# LocationMapper.net
KiCad netlist of a schematic drawn in EAGLE
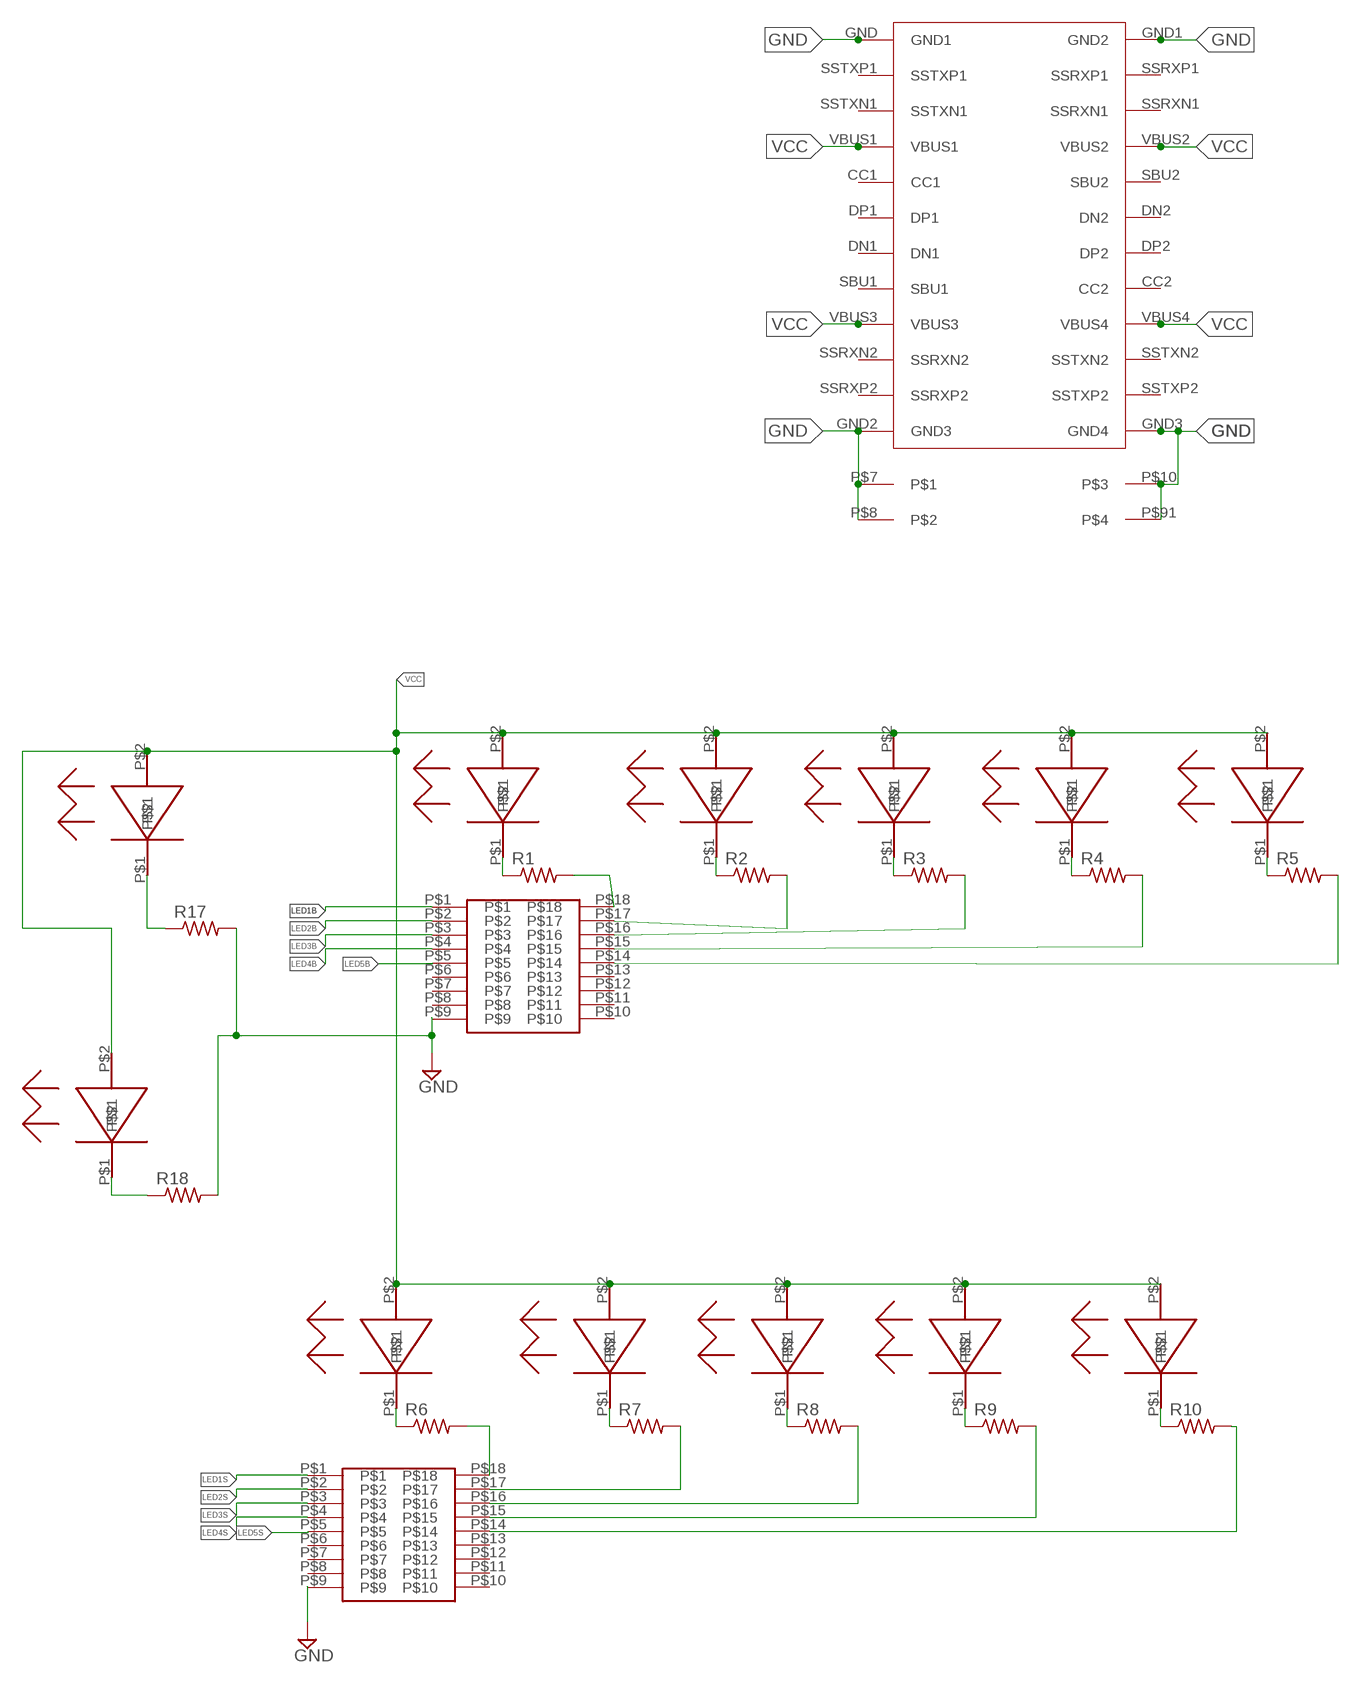
[diagram p0: schematic, sheet 1, part 1 of 2]
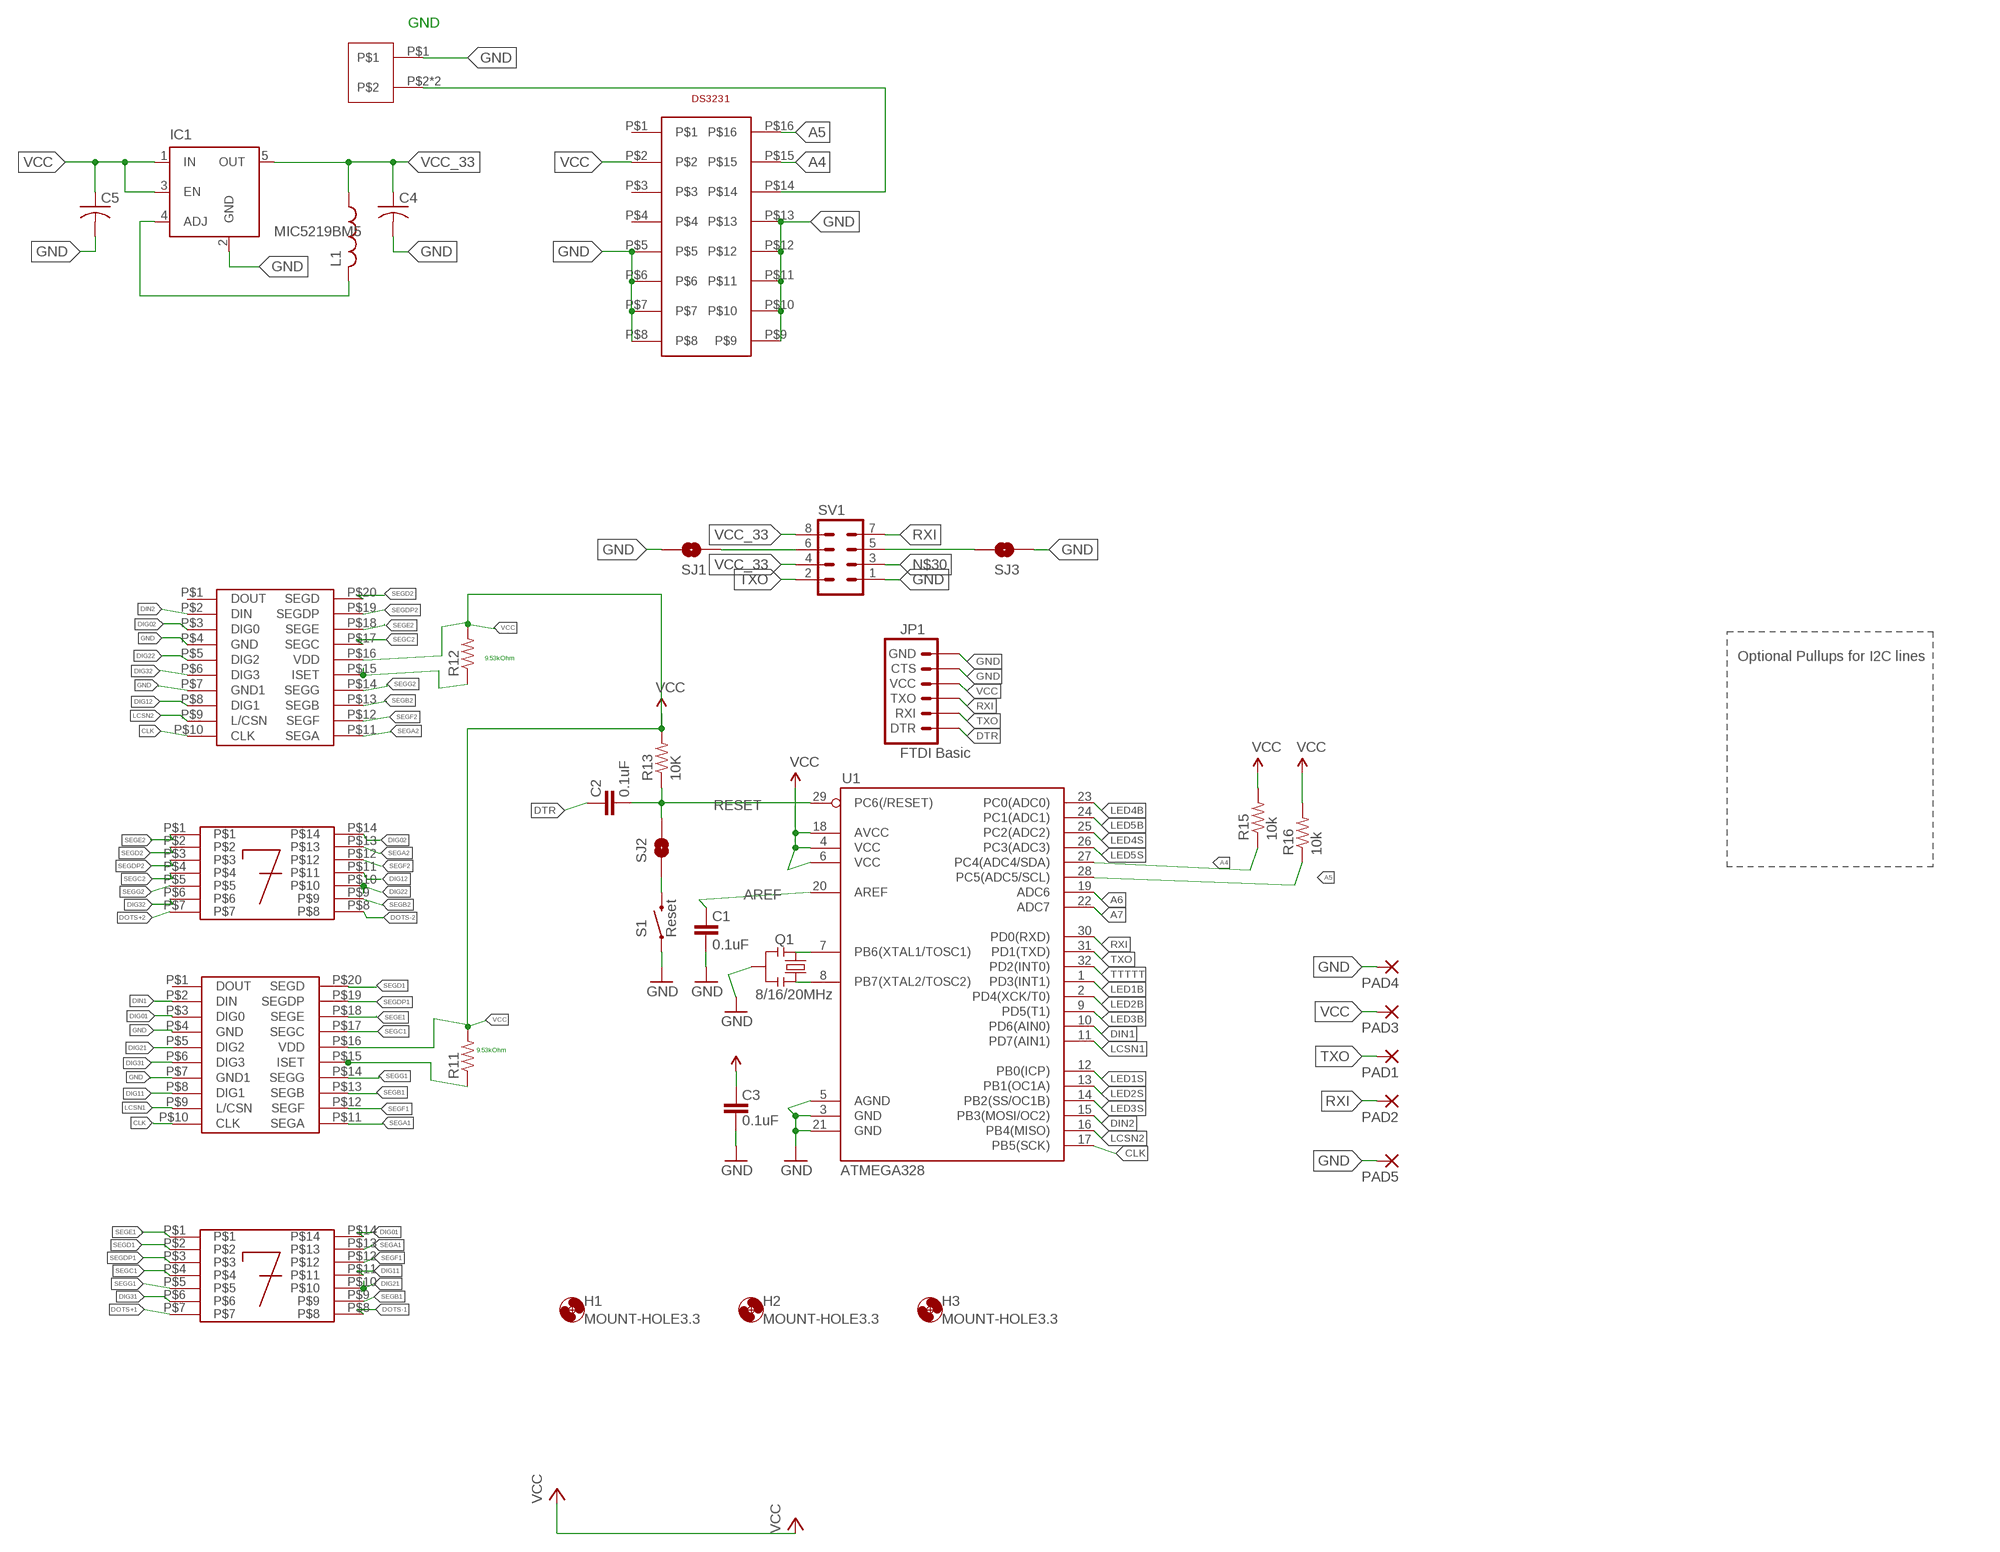
[diagram p1: schematic, sheet 1, part 2 of 2]

(export (version "E")
  (design (tool "Eeschema 10.0.6"))
  (components
    (comp (ref "C1")
      (value "0.1uF")
      (footprint "eagle-import:0603-CAP")
      (libsource (lib "eagle-import") (part "CAP0603-CAP"))
    )
    (comp (ref "C2")
      (value "0.1uF")
      (footprint "eagle-import:0603-CAP")
      (libsource (lib "eagle-import") (part "CAP0603-CAP"))
    )
    (comp (ref "C3")
      (value "0.1uF")
      (footprint "eagle-import:0603-CAP")
      (libsource (lib "eagle-import") (part "CAP0603-CAP"))
    )
    (comp (ref "C4")
      (value "C-USC0805K")
      (footprint "eagle-import:C0805K")
      (libsource (lib "eagle-import") (part "C-USC0805K"))
    )
    (comp (ref "C5")
      (value "C-USC0805K")
      (footprint "eagle-import:C0805K")
      (libsource (lib "eagle-import") (part "C-USC0805K"))
    )
    (comp (ref "H1")
      (value "MOUNT-HOLE3.3")
      (footprint "eagle-import:3,3")
      (libsource (lib "eagle-import") (part "MOUNT-HOLE3.3"))
    )
    (comp (ref "H2")
      (value "MOUNT-HOLE3.3")
      (footprint "eagle-import:3,3")
      (libsource (lib "eagle-import") (part "MOUNT-HOLE3.3"))
    )
    (comp (ref "H3")
      (value "MOUNT-HOLE3.3")
      (footprint "eagle-import:3,3")
      (libsource (lib "eagle-import") (part "MOUNT-HOLE3.3"))
    )
    (comp (ref "IC1")
      (value "MIC5219BM5")
      (footprint "eagle-import:SOT23-5")
      (fields (field (name "MF") "ALTERA CORPORATION") (field (name "MPN") "MIC5219BM5 TR"))
      (libsource (lib "eagle-import") (part "MIC5219BM5"))
    )
    (comp (ref "JP1")
      (value "FTDI Basic")
      (footprint "eagle-import:1X06")
      (libsource (lib "eagle-import") (part "ARDUINO_SERIAL_PROGRAMPTH"))
    )
    (comp (ref "L1")
      (value "L-USL2012C")
      (footprint "eagle-import:L2012C")
      (libsource (lib "eagle-import") (part "L-USL2012C"))
    )
    (comp (ref "PAD1")
      (value "2,54/1,1")
      (footprint "eagle-import:2,54_1,1")
      (libsource (lib "eagle-import") (part "2,54/1,1"))
    )
    (comp (ref "PAD2")
      (value "2,54/1,1")
      (footprint "eagle-import:2,54_1,1")
      (libsource (lib "eagle-import") (part "2,54/1,1"))
    )
    (comp (ref "PAD3")
      (value "2,54/1,1")
      (footprint "eagle-import:2,54_1,1")
      (libsource (lib "eagle-import") (part "2,54/1,1"))
    )
    (comp (ref "PAD4")
      (value "2,54/1,1")
      (footprint "eagle-import:2,54_1,1")
      (libsource (lib "eagle-import") (part "2,54/1,1"))
    )
    (comp (ref "PAD5")
      (value "2,54/1,1")
      (footprint "eagle-import:2,54_1,1")
      (libsource (lib "eagle-import") (part "2,54/1,1"))
    )
    (comp (ref "Q1")
      (value "8/16/20MHz")
      (footprint "eagle-import:RESONATOR-SMD-1_1")
      (libsource (lib "eagle-import") (part "RESONATOR1{colon}1"))
    )
    (comp (ref "R1")
      (value "R-US_R0805")
      (footprint "eagle-import:R0805")
      (libsource (lib "eagle-import") (part "R-US_R0805"))
    )
    (comp (ref "R2")
      (value "R-US_R0805")
      (footprint "eagle-import:R0805")
      (libsource (lib "eagle-import") (part "R-US_R0805"))
    )
    (comp (ref "R3")
      (value "R-US_R0805")
      (footprint "eagle-import:R0805")
      (libsource (lib "eagle-import") (part "R-US_R0805"))
    )
    (comp (ref "R4")
      (value "R-US_R0805")
      (footprint "eagle-import:R0805")
      (libsource (lib "eagle-import") (part "R-US_R0805"))
    )
    (comp (ref "R5")
      (value "R-US_R0805")
      (footprint "eagle-import:R0805")
      (libsource (lib "eagle-import") (part "R-US_R0805"))
    )
    (comp (ref "R6")
      (value "R-US_R0805")
      (footprint "eagle-import:R0805")
      (libsource (lib "eagle-import") (part "R-US_R0805"))
    )
    (comp (ref "R7")
      (value "R-US_R0805")
      (footprint "eagle-import:R0805")
      (libsource (lib "eagle-import") (part "R-US_R0805"))
    )
    (comp (ref "R8")
      (value "R-US_R0805")
      (footprint "eagle-import:R0805")
      (libsource (lib "eagle-import") (part "R-US_R0805"))
    )
    (comp (ref "R9")
      (value "R-US_R0805")
      (footprint "eagle-import:R0805")
      (libsource (lib "eagle-import") (part "R-US_R0805"))
    )
    (comp (ref "R10")
      (value "R-US_R0805")
      (footprint "eagle-import:R0805")
      (libsource (lib "eagle-import") (part "R-US_R0805"))
    )
    (comp (ref "R11")
      (value "R-US_R0805")
      (footprint "eagle-import:R0805")
      (libsource (lib "eagle-import") (part "R-US_R0805"))
    )
    (comp (ref "R12")
      (value "R-US_R0805")
      (footprint "eagle-import:R0805")
      (libsource (lib "eagle-import") (part "R-US_R0805"))
    )
    (comp (ref "R13")
      (value "10K")
      (footprint "eagle-import:0603-RES")
      (libsource (lib "eagle-import") (part "RESISTOR0603-RES"))
    )
    (comp (ref "R15")
      (value "10k")
      (footprint "eagle-import:0603-RES")
      (libsource (lib "eagle-import") (part "RESISTOR0603-RES"))
    )
    (comp (ref "R16")
      (value "10k")
      (footprint "eagle-import:0603-RES")
      (libsource (lib "eagle-import") (part "RESISTOR0603-RES"))
    )
    (comp (ref "R17")
      (value "R-US_R0805")
      (footprint "eagle-import:R0805")
      (libsource (lib "eagle-import") (part "R-US_R0805"))
    )
    (comp (ref "R18")
      (value "R-US_R0805")
      (footprint "eagle-import:R0805")
      (libsource (lib "eagle-import") (part "R-US_R0805"))
    )
    (comp (ref "S1")
      (value "Reset")
      (footprint "eagle-import:TACTILE-SWITCH-SMD-ALT01")
      (libsource (lib "eagle-import") (part "SWITCH-MOMENTARY-2SMD-ALT01"))
    )
    (comp (ref "SJ1")
      (value "SOLDERJUMPERNC")
      (footprint "eagle-import:SJ_2S")
      (libsource (lib "eagle-import") (part "SOLDERJUMPERNC"))
    )
    (comp (ref "SJ2")
      (value "SOLDERJUMPERNC")
      (footprint "eagle-import:SJ_2S")
      (libsource (lib "eagle-import") (part "SOLDERJUMPERNC"))
    )
    (comp (ref "SJ3")
      (value "SOLDERJUMPERNC")
      (footprint "eagle-import:SJ_2S")
      (libsource (lib "eagle-import") (part "SOLDERJUMPERNC"))
    )
    (comp (ref "SV1")
      (value "MA04-2")
      (footprint "eagle-import:MA04-2")
      (libsource (lib "eagle-import") (part "MA04-2"))
    )
    (comp (ref "U$1")
      (value "LED_LM")
      (footprint "eagle-import:LED_LM")
      (libsource (lib "eagle-import") (part "LED_LM"))
    )
    (comp (ref "U$2")
      (value "LED_LM")
      (footprint "eagle-import:LED_LM")
      (libsource (lib "eagle-import") (part "LED_LM"))
    )
    (comp (ref "U$3")
      (value "LED_LM")
      (footprint "eagle-import:LED_LM")
      (libsource (lib "eagle-import") (part "LED_LM"))
    )
    (comp (ref "U$4")
      (value "LED_LM")
      (footprint "eagle-import:LED_LM")
      (libsource (lib "eagle-import") (part "LED_LM"))
    )
    (comp (ref "U$5")
      (value "LED_LM")
      (footprint "eagle-import:LED_LM")
      (libsource (lib "eagle-import") (part "LED_LM"))
    )
    (comp (ref "U$6")
      (value "LED_LM")
      (footprint "eagle-import:LED_LM")
      (libsource (lib "eagle-import") (part "LED_LM"))
    )
    (comp (ref "U$7")
      (value "LED_LM")
      (footprint "eagle-import:LED_LM")
      (libsource (lib "eagle-import") (part "LED_LM"))
    )
    (comp (ref "U$8")
      (value "LED_LM")
      (footprint "eagle-import:LED_LM")
      (libsource (lib "eagle-import") (part "LED_LM"))
    )
    (comp (ref "U$9")
      (value "LED_LM")
      (footprint "eagle-import:LED_LM")
      (libsource (lib "eagle-import") (part "LED_LM"))
    )
    (comp (ref "U$10")
      (value "LED_LM")
      (footprint "eagle-import:LED_LM")
      (libsource (lib "eagle-import") (part "LED_LM"))
    )
    (comp (ref "U$11")
      (value "ULN2803A")
      (footprint "eagle-import:ULN2803A")
      (libsource (lib "eagle-import") (part "ULN2803A"))
    )
    (comp (ref "U$12")
      (value "ULN2803A")
      (footprint "eagle-import:ULN2803A")
      (libsource (lib "eagle-import") (part "ULN2803A"))
    )
    (comp (ref "U$13")
      (value "7SEG")
      (footprint "eagle-import:7SEG")
      (libsource (lib "eagle-import") (part "7SEG"))
    )
    (comp (ref "U$14")
      (value "7SEG")
      (footprint "eagle-import:7SEG")
      (libsource (lib "eagle-import") (part "7SEG"))
    )
    (comp (ref "U$15")
      (value "7SEG_DRIVER")
      (footprint "eagle-import:SO20W")
      (libsource (lib "eagle-import") (part "7SEG_DRIVER"))
    )
    (comp (ref "U$16")
      (value "7SEG_DRIVER")
      (footprint "eagle-import:SO20W")
      (libsource (lib "eagle-import") (part "7SEG_DRIVER"))
    )
    (comp (ref "U$17")
      (value "LED_LM")
      (footprint "eagle-import:LED_LM")
      (libsource (lib "eagle-import") (part "LED_LM"))
    )
    (comp (ref "U$18")
      (value "LED_LM")
      (footprint "eagle-import:LED_LM")
      (libsource (lib "eagle-import") (part "LED_LM"))
    )
    (comp (ref "U$19")
      (value "DS3231_BACK")
      (footprint "eagle-import:DS3231_BACK")
      (libsource (lib "eagle-import") (part "DS3231_BACK"))
    )
    (comp (ref "U$20")
      (value "CR2032")
      (footprint "eagle-import:CR2032")
      (libsource (lib "eagle-import") (part "CR2032"))
    )
    (comp (ref "U$21")
      (value "USB-C")
      (footprint "eagle-import:USB-C")
      (libsource (lib "eagle-import") (part "USB-C"))
    )
    (comp (ref "U1")
      (value "ATMEGA328")
      (footprint "eagle-import:TQFP32-08")
      (libsource (lib "eagle-import") (part "ATMEGA168"))
    )
  )
  (nets
    (net (code "1") (name "/AREF") (class "Default")
      (node (ref "C1") (pin "2") (pinfunction "2_2") (pintype "passive"))
      (node (ref "U1") (pin "20") (pinfunction "AREF_20") (pintype "bidirectional"))
    )
    (net (code "2") (name "/RESET") (class "Default")
      (node (ref "C2") (pin "1") (pinfunction "1_1") (pintype "passive"))
      (node (ref "R13") (pin "1") (pinfunction "1_1") (pintype "passive"))
      (node (ref "SJ2") (pin "2") (pinfunction "2_2") (pintype "passive"))
      (node (ref "U1") (pin "29") (pinfunction "PC6(/RESET)_29") (pintype "bidirectional"))
    )
    (net (code "3") (name "A4") (class "Default")
      (node (ref "R15") (pin "1") (pinfunction "1_1") (pintype "passive"))
      (node (ref "U$19") (pin "P$15") (pinfunction "P$15_P$15") (pintype "bidirectional"))
      (node (ref "U1") (pin "27") (pinfunction "PC4(ADC4/SDA)_27") (pintype "bidirectional"))
    )
    (net (code "4") (name "A5") (class "Default")
      (node (ref "R16") (pin "1") (pinfunction "1_1") (pintype "passive"))
      (node (ref "U$19") (pin "P$16") (pinfunction "P$16_P$16") (pintype "bidirectional"))
      (node (ref "U1") (pin "28") (pinfunction "PC5(ADC5/SCL)_28") (pintype "bidirectional"))
    )
    (net (code "5") (name "A6") (class "Default")
      (node (ref "U1") (pin "19") (pinfunction "ADC6_19") (pintype "bidirectional"))
    )
    (net (code "6") (name "A7") (class "Default")
      (node (ref "U1") (pin "22") (pinfunction "ADC7_22") (pintype "bidirectional"))
    )
    (net (code "7") (name "CLK") (class "Default")
      (node (ref "U$15") (pin "P$10") (pinfunction "CLK_P$10") (pintype "bidirectional"))
      (node (ref "U$16") (pin "P$10") (pinfunction "CLK_P$10") (pintype "bidirectional"))
      (node (ref "U1") (pin "17") (pinfunction "PB5(SCK)_17") (pintype "bidirectional"))
    )
    (net (code "8") (name "DIG01") (class "Default")
      (node (ref "U$14") (pin "P$14") (pinfunction "P$14_P$14") (pintype "bidirectional"))
      (node (ref "U$15") (pin "P$3") (pinfunction "DIG0_P$3") (pintype "bidirectional"))
    )
    (net (code "9") (name "DIG02") (class "Default")
      (node (ref "U$13") (pin "P$14") (pinfunction "P$14_P$14") (pintype "bidirectional"))
      (node (ref "U$16") (pin "P$3") (pinfunction "DIG0_P$3") (pintype "bidirectional"))
    )
    (net (code "10") (name "DIG11") (class "Default")
      (node (ref "U$14") (pin "P$11") (pinfunction "P$11_P$11") (pintype "bidirectional"))
      (node (ref "U$15") (pin "P$8") (pinfunction "DIG1_P$8") (pintype "bidirectional"))
    )
    (net (code "11") (name "DIG12") (class "Default")
      (node (ref "U$13") (pin "P$11") (pinfunction "P$11_P$11") (pintype "bidirectional"))
      (node (ref "U$16") (pin "P$8") (pinfunction "DIG1_P$8") (pintype "bidirectional"))
    )
    (net (code "12") (name "DIG21") (class "Default")
      (node (ref "U$14") (pin "P$10") (pinfunction "P$10_P$10") (pintype "bidirectional"))
      (node (ref "U$15") (pin "P$5") (pinfunction "DIG2_P$5") (pintype "bidirectional"))
    )
    (net (code "13") (name "DIG22") (class "Default")
      (node (ref "U$13") (pin "P$10") (pinfunction "P$10_P$10") (pintype "bidirectional"))
      (node (ref "U$16") (pin "P$5") (pinfunction "DIG2_P$5") (pintype "bidirectional"))
    )
    (net (code "14") (name "DIG31") (class "Default")
      (node (ref "U$14") (pin "P$6") (pinfunction "P$6_P$6") (pintype "bidirectional"))
      (node (ref "U$15") (pin "P$6") (pinfunction "DIG3_P$6") (pintype "bidirectional"))
    )
    (net (code "15") (name "DIG32") (class "Default")
      (node (ref "U$13") (pin "P$6") (pinfunction "P$6_P$6") (pintype "bidirectional"))
      (node (ref "U$16") (pin "P$6") (pinfunction "DIG3_P$6") (pintype "bidirectional"))
    )
    (net (code "16") (name "DIN1") (class "Default")
      (node (ref "U$15") (pin "P$2") (pinfunction "DIN_P$2") (pintype "bidirectional"))
      (node (ref "U1") (pin "10") (pinfunction "PD6(AIN0)_10") (pintype "bidirectional"))
    )
    (net (code "17") (name "DIN2") (class "Default")
      (node (ref "U$16") (pin "P$2") (pinfunction "DIN_P$2") (pintype "bidirectional"))
      (node (ref "U1") (pin "15") (pinfunction "PB3(MOSI/OC2)_15") (pintype "bidirectional"))
    )
    (net (code "18") (name "DOTS+1") (class "Default")
      (node (ref "U$14") (pin "P$7") (pinfunction "P$7_P$7") (pintype "bidirectional"))
    )
    (net (code "19") (name "DOTS+2") (class "Default")
      (node (ref "U$13") (pin "P$7") (pinfunction "P$7_P$7") (pintype "bidirectional"))
    )
    (net (code "20") (name "DOTS-1") (class "Default")
      (node (ref "U$14") (pin "P$8") (pinfunction "P$8_P$8") (pintype "bidirectional"))
    )
    (net (code "21") (name "DOTS-2") (class "Default")
      (node (ref "U$13") (pin "P$8") (pinfunction "P$8_P$8") (pintype "bidirectional"))
    )
    (net (code "22") (name "DTR") (class "Default")
      (node (ref "C2") (pin "2") (pinfunction "2_2") (pintype "passive"))
      (node (ref "JP1") (pin "1") (pinfunction "DTR_1") (pintype "passive"))
    )
    (net (code "23") (name "GND") (class "Default")
      (node (ref "C1") (pin "1") (pinfunction "1_1") (pintype "passive"))
      (node (ref "C3") (pin "1") (pinfunction "1_1") (pintype "passive"))
      (node (ref "C4") (pin "2") (pinfunction "2_2") (pintype "passive"))
      (node (ref "C5") (pin "2") (pinfunction "2_2") (pintype "passive"))
      (node (ref "IC1") (pin "2") (pinfunction "GND_2") (pintype "power_in"))
      (node (ref "JP1") (pin "5") (pinfunction "CTS_5") (pintype "passive"))
      (node (ref "JP1") (pin "6") (pinfunction "GND_6") (pintype "passive"))
      (node (ref "PAD4") (pin "1") (pinfunction "P_1") (pintype "passive"))
      (node (ref "PAD5") (pin "1") (pinfunction "P_1") (pintype "passive"))
      (node (ref "Q1") (pin "2") (pinfunction "2_2") (pintype "passive"))
      (node (ref "R17") (pin "2") (pinfunction "2_2") (pintype "passive"))
      (node (ref "R18") (pin "2") (pinfunction "2_2") (pintype "passive"))
      (node (ref "S1") (pin "1") (pinfunction "1_1") (pintype "passive"))
      (node (ref "S1") (pin "2") (pinfunction "1_2") (pintype "passive"))
      (node (ref "SJ1") (pin "2") (pinfunction "2_2") (pintype "passive"))
      (node (ref "SJ3") (pin "1") (pinfunction "1_1") (pintype "passive"))
      (node (ref "SV1") (pin "1") (pinfunction "1_1") (pintype "passive"))
      (node (ref "U$11") (pin "P$9") (pinfunction "P$9_P$9") (pintype "bidirectional"))
      (node (ref "U$12") (pin "P$9") (pinfunction "P$9_P$9") (pintype "bidirectional"))
      (node (ref "U$15") (pin "P$4") (pinfunction "GND_P$4") (pintype "bidirectional"))
      (node (ref "U$15") (pin "P$7") (pinfunction "GND1_P$7") (pintype "bidirectional"))
      (node (ref "U$16") (pin "P$4") (pinfunction "GND_P$4") (pintype "bidirectional"))
      (node (ref "U$16") (pin "P$7") (pinfunction "GND1_P$7") (pintype "bidirectional"))
      (node (ref "U$19") (pin "P$10") (pinfunction "P$10_P$10") (pintype "bidirectional"))
      (node (ref "U$19") (pin "P$11") (pinfunction "P$11_P$11") (pintype "bidirectional"))
      (node (ref "U$19") (pin "P$12") (pinfunction "P$12_P$12") (pintype "bidirectional"))
      (node (ref "U$19") (pin "P$13") (pinfunction "P$13_P$13") (pintype "bidirectional"))
      (node (ref "U$19") (pin "P$5") (pinfunction "P$5_P$5") (pintype "bidirectional"))
      (node (ref "U$19") (pin "P$6") (pinfunction "P$6_P$6") (pintype "bidirectional"))
      (node (ref "U$19") (pin "P$7") (pinfunction "P$7_P$7") (pintype "bidirectional"))
      (node (ref "U$19") (pin "P$8") (pinfunction "P$8_P$8") (pintype "bidirectional"))
      (node (ref "U$19") (pin "P$9") (pinfunction "P$9_P$9") (pintype "bidirectional"))
      (node (ref "U$20") (pin "P$1") (pinfunction "P$1_P$1") (pintype "bidirectional"))
      (node (ref "U$21") (pin "GND") (pinfunction "GND1_GND") (pintype "bidirectional"))
      (node (ref "U$21") (pin "GND1") (pinfunction "GND2_GND1") (pintype "bidirectional"))
      (node (ref "U$21") (pin "GND2") (pinfunction "GND3_GND2") (pintype "bidirectional"))
      (node (ref "U$21") (pin "GND3") (pinfunction "GND4_GND3") (pintype "bidirectional"))
      (node (ref "U$21") (pin "P$10") (pinfunction "P$3_P$10") (pintype "bidirectional"))
      (node (ref "U$21") (pin "P$7") (pinfunction "P$1_P$7") (pintype "bidirectional"))
      (node (ref "U$21") (pin "P$8") (pinfunction "P$2_P$8") (pintype "bidirectional"))
      (node (ref "U$21") (pin "P$91") (pinfunction "P$4_P$91") (pintype "bidirectional"))
      (node (ref "U1") (pin "21") (pinfunction "GND_21") (pintype "bidirectional"))
      (node (ref "U1") (pin "3") (pinfunction "GND_3") (pintype "bidirectional"))
      (node (ref "U1") (pin "5") (pinfunction "AGND_5") (pintype "bidirectional"))
    )
    (net (code "24") (name "LCSN1") (class "Default")
      (node (ref "U$15") (pin "P$9") (pinfunction "L/CSN_P$9") (pintype "bidirectional"))
      (node (ref "U1") (pin "11") (pinfunction "PD7(AIN1)_11") (pintype "bidirectional"))
    )
    (net (code "25") (name "LCSN2") (class "Default")
      (node (ref "U$16") (pin "P$9") (pinfunction "L/CSN_P$9") (pintype "bidirectional"))
      (node (ref "U1") (pin "16") (pinfunction "PB4(MISO)_16") (pintype "bidirectional"))
    )
    (net (code "26") (name "LED1B") (class "Default")
      (node (ref "U$11") (pin "P$1") (pinfunction "P$1_P$1") (pintype "bidirectional"))
      (node (ref "U1") (pin "1") (pinfunction "PD3(INT1)_1") (pintype "bidirectional"))
    )
    (net (code "27") (name "LED1S") (class "Default")
      (node (ref "U$12") (pin "P$1") (pinfunction "P$1_P$1") (pintype "bidirectional"))
      (node (ref "U1") (pin "12") (pinfunction "PB0(ICP)_12") (pintype "bidirectional"))
    )
    (net (code "28") (name "LED2B") (class "Default")
      (node (ref "U$11") (pin "P$2") (pinfunction "P$2_P$2") (pintype "bidirectional"))
      (node (ref "U1") (pin "2") (pinfunction "PD4(XCK/T0)_2") (pintype "bidirectional"))
    )
    (net (code "29") (name "LED2S") (class "Default")
      (node (ref "U$12") (pin "P$2") (pinfunction "P$2_P$2") (pintype "bidirectional"))
      (node (ref "U1") (pin "13") (pinfunction "PB1(OC1A)_13") (pintype "bidirectional"))
    )
    (net (code "30") (name "LED3B") (class "Default")
      (node (ref "U$11") (pin "P$3") (pinfunction "P$3_P$3") (pintype "bidirectional"))
      (node (ref "U1") (pin "9") (pinfunction "PD5(T1)_9") (pintype "bidirectional"))
    )
    (net (code "31") (name "LED3S") (class "Default")
      (node (ref "U$12") (pin "P$3") (pinfunction "P$3_P$3") (pintype "bidirectional"))
      (node (ref "U1") (pin "14") (pinfunction "PB2(SS/OC1B)_14") (pintype "bidirectional"))
    )
    (net (code "32") (name "LED4B") (class "Default")
      (node (ref "U$11") (pin "P$4") (pinfunction "P$4_P$4") (pintype "bidirectional"))
      (node (ref "U1") (pin "23") (pinfunction "PC0(ADC0)_23") (pintype "bidirectional"))
    )
    (net (code "33") (name "LED4S") (class "Default")
      (node (ref "U$12") (pin "P$4") (pinfunction "P$4_P$4") (pintype "bidirectional"))
      (node (ref "U1") (pin "25") (pinfunction "PC2(ADC2)_25") (pintype "bidirectional"))
    )
    (net (code "34") (name "LED5B") (class "Default")
      (node (ref "U$11") (pin "P$5") (pinfunction "P$5_P$5") (pintype "bidirectional"))
      (node (ref "U1") (pin "24") (pinfunction "PC1(ADC1)_24") (pintype "bidirectional"))
    )
    (net (code "35") (name "LED5S") (class "Default")
      (node (ref "U$12") (pin "P$5") (pinfunction "P$5_P$5") (pintype "bidirectional"))
      (node (ref "U1") (pin "26") (pinfunction "PC3(ADC3)_26") (pintype "bidirectional"))
    )
    (net (code "36") (name "N$30") (class "Default")
      (node (ref "SV1") (pin "3") (pinfunction "3_3") (pintype "passive"))
    )
    (net (code "37") (name "Net-(IC1-ADJ)") (class "Default")
      (node (ref "IC1") (pin "4") (pinfunction "ADJ_4") (pintype "passive"))
      (node (ref "L1") (pin "2") (pinfunction "2_2") (pintype "passive"))
    )
    (net (code "38") (name "Net-(R1-Pad1)") (class "Default")
      (node (ref "R1") (pin "1") (pinfunction "1_1") (pintype "passive"))
      (node (ref "U$6") (pin "P$1") (pinfunction "P$1_P$1") (pintype "bidirectional"))
    )
    (net (code "39") (name "Net-(R1-Pad2)") (class "Default")
      (node (ref "R1") (pin "2") (pinfunction "2_2") (pintype "passive"))
      (node (ref "U$11") (pin "P$18") (pinfunction "P$18_P$18") (pintype "bidirectional"))
    )
    (net (code "40") (name "Net-(R2-Pad1)") (class "Default")
      (node (ref "R2") (pin "1") (pinfunction "1_1") (pintype "passive"))
      (node (ref "U$7") (pin "P$1") (pinfunction "P$1_P$1") (pintype "bidirectional"))
    )
    (net (code "41") (name "Net-(R2-Pad2)") (class "Default")
      (node (ref "R2") (pin "2") (pinfunction "2_2") (pintype "passive"))
      (node (ref "U$11") (pin "P$17") (pinfunction "P$17_P$17") (pintype "bidirectional"))
    )
    (net (code "42") (name "Net-(R3-Pad1)") (class "Default")
      (node (ref "R3") (pin "1") (pinfunction "1_1") (pintype "passive"))
      (node (ref "U$8") (pin "P$1") (pinfunction "P$1_P$1") (pintype "bidirectional"))
    )
    (net (code "43") (name "Net-(R3-Pad2)") (class "Default")
      (node (ref "R3") (pin "2") (pinfunction "2_2") (pintype "passive"))
      (node (ref "U$11") (pin "P$16") (pinfunction "P$16_P$16") (pintype "bidirectional"))
    )
    (net (code "44") (name "Net-(R4-Pad1)") (class "Default")
      (node (ref "R4") (pin "1") (pinfunction "1_1") (pintype "passive"))
      (node (ref "U$9") (pin "P$1") (pinfunction "P$1_P$1") (pintype "bidirectional"))
    )
    (net (code "45") (name "Net-(R4-Pad2)") (class "Default")
      (node (ref "R4") (pin "2") (pinfunction "2_2") (pintype "passive"))
      (node (ref "U$11") (pin "P$15") (pinfunction "P$15_P$15") (pintype "bidirectional"))
    )
    (net (code "46") (name "Net-(R5-Pad1)") (class "Default")
      (node (ref "R5") (pin "1") (pinfunction "1_1") (pintype "passive"))
      (node (ref "U$10") (pin "P$1") (pinfunction "P$1_P$1") (pintype "bidirectional"))
    )
    (net (code "47") (name "Net-(R5-Pad2)") (class "Default")
      (node (ref "R5") (pin "2") (pinfunction "2_2") (pintype "passive"))
      (node (ref "U$11") (pin "P$14") (pinfunction "P$14_P$14") (pintype "bidirectional"))
    )
    (net (code "48") (name "Net-(R6-Pad1)") (class "Default")
      (node (ref "R6") (pin "1") (pinfunction "1_1") (pintype "passive"))
      (node (ref "U$1") (pin "P$1") (pinfunction "P$1_P$1") (pintype "bidirectional"))
    )
    (net (code "49") (name "Net-(R6-Pad2)") (class "Default")
      (node (ref "R6") (pin "2") (pinfunction "2_2") (pintype "passive"))
      (node (ref "U$12") (pin "P$18") (pinfunction "P$18_P$18") (pintype "bidirectional"))
    )
    (net (code "50") (name "Net-(R7-Pad1)") (class "Default")
      (node (ref "R7") (pin "1") (pinfunction "1_1") (pintype "passive"))
      (node (ref "U$2") (pin "P$1") (pinfunction "P$1_P$1") (pintype "bidirectional"))
    )
    (net (code "51") (name "Net-(R7-Pad2)") (class "Default")
      (node (ref "R7") (pin "2") (pinfunction "2_2") (pintype "passive"))
      (node (ref "U$12") (pin "P$17") (pinfunction "P$17_P$17") (pintype "bidirectional"))
    )
    (net (code "52") (name "Net-(R8-Pad1)") (class "Default")
      (node (ref "R8") (pin "1") (pinfunction "1_1") (pintype "passive"))
      (node (ref "U$3") (pin "P$1") (pinfunction "P$1_P$1") (pintype "bidirectional"))
    )
    (net (code "53") (name "Net-(R8-Pad2)") (class "Default")
      (node (ref "R8") (pin "2") (pinfunction "2_2") (pintype "passive"))
      (node (ref "U$12") (pin "P$16") (pinfunction "P$16_P$16") (pintype "bidirectional"))
    )
    (net (code "54") (name "Net-(R9-Pad1)") (class "Default")
      (node (ref "R9") (pin "1") (pinfunction "1_1") (pintype "passive"))
      (node (ref "U$4") (pin "P$1") (pinfunction "P$1_P$1") (pintype "bidirectional"))
    )
    (net (code "55") (name "Net-(R9-Pad2)") (class "Default")
      (node (ref "R9") (pin "2") (pinfunction "2_2") (pintype "passive"))
      (node (ref "U$12") (pin "P$15") (pinfunction "P$15_P$15") (pintype "bidirectional"))
    )
    (net (code "56") (name "Net-(R10-Pad1)") (class "Default")
      (node (ref "R10") (pin "1") (pinfunction "1_1") (pintype "passive"))
      (node (ref "U$5") (pin "P$1") (pinfunction "P$1_P$1") (pintype "bidirectional"))
    )
    (net (code "57") (name "Net-(R10-Pad2)") (class "Default")
      (node (ref "R10") (pin "2") (pinfunction "2_2") (pintype "passive"))
      (node (ref "U$12") (pin "P$14") (pinfunction "P$14_P$14") (pintype "bidirectional"))
    )
    (net (code "58") (name "Net-(R17-Pad1)") (class "Default")
      (node (ref "R17") (pin "1") (pinfunction "1_1") (pintype "passive"))
      (node (ref "U$17") (pin "P$1") (pinfunction "P$1_P$1") (pintype "bidirectional"))
    )
    (net (code "59") (name "Net-(R18-Pad1)") (class "Default")
      (node (ref "R18") (pin "1") (pinfunction "1_1") (pintype "passive"))
      (node (ref "U$18") (pin "P$1") (pinfunction "P$1_P$1") (pintype "bidirectional"))
    )
    (net (code "60") (name "Net-(S1-2-Pad3)") (class "Default")
      (node (ref "S1") (pin "3") (pinfunction "2_3") (pintype "passive"))
      (node (ref "S1") (pin "4") (pinfunction "2_4") (pintype "passive"))
      (node (ref "SJ2") (pin "1") (pinfunction "1_1") (pintype "passive"))
    )
    (net (code "61") (name "Net-(SJ1-Pad1)") (class "Default")
      (node (ref "SJ1") (pin "1") (pinfunction "1_1") (pintype "passive"))
      (node (ref "SV1") (pin "6") (pinfunction "6_6") (pintype "passive"))
    )
    (net (code "62") (name "Net-(SJ3-Pad2)") (class "Default")
      (node (ref "SJ3") (pin "2") (pinfunction "2_2") (pintype "passive"))
      (node (ref "SV1") (pin "5") (pinfunction "5_5") (pintype "passive"))
    )
    (net (code "63") (name "Net-(U$15-ISET)") (class "Default")
      (node (ref "R11") (pin "1") (pinfunction "1_1") (pintype "passive"))
      (node (ref "U$15") (pin "P$15") (pinfunction "ISET_P$15") (pintype "bidirectional"))
    )
    (net (code "64") (name "Net-(U$16-ISET)") (class "Default")
      (node (ref "R12") (pin "1") (pinfunction "1_1") (pintype "passive"))
      (node (ref "U$16") (pin "P$15") (pinfunction "ISET_P$15") (pintype "bidirectional"))
    )
    (net (code "65") (name "Net-(U$19-PadP$14)") (class "Default")
      (node (ref "U$19") (pin "P$14") (pinfunction "P$14_P$14") (pintype "bidirectional"))
      (node (ref "U$20") (pin "P$2") (pinfunction "P$2_P$2") (pintype "bidirectional"))
      (node (ref "U$20") (pin "P$3") (pinfunction "P$2_P$3") (pintype "bidirectional"))
    )
    (net (code "66") (name "Net-(U1-PB6(XTAL1{slash}TOSC1))") (class "Default")
      (node (ref "Q1") (pin "1") (pinfunction "1_1") (pintype "passive"))
      (node (ref "U1") (pin "7") (pinfunction "PB6(XTAL1/TOSC1)_7") (pintype "bidirectional"))
    )
    (net (code "67") (name "Net-(U1-PB7(XTAL2{slash}TOSC2))") (class "Default")
      (node (ref "Q1") (pin "3") (pinfunction "3_3") (pintype "passive"))
      (node (ref "U1") (pin "8") (pinfunction "PB7(XTAL2/TOSC2)_8") (pintype "bidirectional"))
    )
    (net (code "68") (name "RXI") (class "Default")
      (node (ref "JP1") (pin "3") (pinfunction "TXO_3") (pintype "passive"))
      (node (ref "PAD2") (pin "1") (pinfunction "P_1") (pintype "passive"))
      (node (ref "SV1") (pin "7") (pinfunction "7_7") (pintype "passive"))
      (node (ref "U1") (pin "30") (pinfunction "PD0(RXD)_30") (pintype "bidirectional"))
    )
    (net (code "69") (name "SEGA1") (class "Default")
      (node (ref "U$14") (pin "P$13") (pinfunction "P$13_P$13") (pintype "bidirectional"))
      (node (ref "U$15") (pin "P$11") (pinfunction "SEGA_P$11") (pintype "bidirectional"))
    )
    (net (code "70") (name "SEGA2") (class "Default")
      (node (ref "U$13") (pin "P$13") (pinfunction "P$13_P$13") (pintype "bidirectional"))
      (node (ref "U$16") (pin "P$11") (pinfunction "SEGA_P$11") (pintype "bidirectional"))
    )
    (net (code "71") (name "SEGB1") (class "Default")
      (node (ref "U$14") (pin "P$9") (pinfunction "P$9_P$9") (pintype "bidirectional"))
      (node (ref "U$15") (pin "P$13") (pinfunction "SEGB_P$13") (pintype "bidirectional"))
    )
    (net (code "72") (name "SEGB2") (class "Default")
      (node (ref "U$13") (pin "P$9") (pinfunction "P$9_P$9") (pintype "bidirectional"))
      (node (ref "U$16") (pin "P$13") (pinfunction "SEGB_P$13") (pintype "bidirectional"))
    )
    (net (code "73") (name "SEGC1") (class "Default")
      (node (ref "U$14") (pin "P$4") (pinfunction "P$4_P$4") (pintype "bidirectional"))
      (node (ref "U$15") (pin "P$17") (pinfunction "SEGC_P$17") (pintype "bidirectional"))
    )
    (net (code "74") (name "SEGC2") (class "Default")
      (node (ref "U$13") (pin "P$4") (pinfunction "P$4_P$4") (pintype "bidirectional"))
      (node (ref "U$16") (pin "P$17") (pinfunction "SEGC_P$17") (pintype "bidirectional"))
    )
    (net (code "75") (name "SEGD1") (class "Default")
      (node (ref "U$14") (pin "P$2") (pinfunction "P$2_P$2") (pintype "bidirectional"))
      (node (ref "U$15") (pin "P$20") (pinfunction "SEGD_P$20") (pintype "bidirectional"))
    )
    (net (code "76") (name "SEGD2") (class "Default")
      (node (ref "U$13") (pin "P$2") (pinfunction "P$2_P$2") (pintype "bidirectional"))
      (node (ref "U$16") (pin "P$20") (pinfunction "SEGD_P$20") (pintype "bidirectional"))
    )
    (net (code "77") (name "SEGDP1") (class "Default")
      (node (ref "U$14") (pin "P$3") (pinfunction "P$3_P$3") (pintype "bidirectional"))
      (node (ref "U$15") (pin "P$19") (pinfunction "SEGDP_P$19") (pintype "bidirectional"))
    )
    (net (code "78") (name "SEGDP2") (class "Default")
      (node (ref "U$13") (pin "P$3") (pinfunction "P$3_P$3") (pintype "bidirectional"))
      (node (ref "U$16") (pin "P$19") (pinfunction "SEGDP_P$19") (pintype "bidirectional"))
    )
    (net (code "79") (name "SEGE1") (class "Default")
      (node (ref "U$14") (pin "P$1") (pinfunction "P$1_P$1") (pintype "bidirectional"))
      (node (ref "U$15") (pin "P$18") (pinfunction "SEGE_P$18") (pintype "bidirectional"))
    )
    (net (code "80") (name "SEGE2") (class "Default")
      (node (ref "U$13") (pin "P$1") (pinfunction "P$1_P$1") (pintype "bidirectional"))
      (node (ref "U$16") (pin "P$18") (pinfunction "SEGE_P$18") (pintype "bidirectional"))
    )
    (net (code "81") (name "SEGF1") (class "Default")
      (node (ref "U$14") (pin "P$12") (pinfunction "P$12_P$12") (pintype "bidirectional"))
      (node (ref "U$15") (pin "P$12") (pinfunction "SEGF_P$12") (pintype "bidirectional"))
    )
    (net (code "82") (name "SEGF2") (class "Default")
      (node (ref "U$13") (pin "P$12") (pinfunction "P$12_P$12") (pintype "bidirectional"))
      (node (ref "U$16") (pin "P$12") (pinfunction "SEGF_P$12") (pintype "bidirectional"))
    )
    (net (code "83") (name "SEGG1") (class "Default")
      (node (ref "U$14") (pin "P$5") (pinfunction "P$5_P$5") (pintype "bidirectional"))
      (node (ref "U$15") (pin "P$14") (pinfunction "SEGG_P$14") (pintype "bidirectional"))
    )
    (net (code "84") (name "SEGG2") (class "Default")
      (node (ref "U$13") (pin "P$5") (pinfunction "P$5_P$5") (pintype "bidirectional"))
      (node (ref "U$16") (pin "P$14") (pinfunction "SEGG_P$14") (pintype "bidirectional"))
    )
    (net (code "85") (name "TTTTT") (class "Default")
      (node (ref "U1") (pin "32") (pinfunction "PD2(INT0)_32") (pintype "bidirectional"))
    )
    (net (code "86") (name "TXO") (class "Default")
      (node (ref "JP1") (pin "2") (pinfunction "RXI_2") (pintype "passive"))
      (node (ref "PAD1") (pin "1") (pinfunction "P_1") (pintype "passive"))
      (node (ref "SV1") (pin "2") (pinfunction "2_2") (pintype "passive"))
      (node (ref "U1") (pin "31") (pinfunction "PD1(TXD)_31") (pintype "bidirectional"))
    )
    (net (code "87") (name "VCC") (class "Default")
      (node (ref "C3") (pin "2") (pinfunction "2_2") (pintype "passive"))
      (node (ref "C5") (pin "1") (pinfunction "1_1") (pintype "passive"))
      (node (ref "IC1") (pin "1") (pinfunction "IN_1") (pintype "input"))
      (node (ref "IC1") (pin "3") (pinfunction "EN_3") (pintype "input"))
      (node (ref "JP1") (pin "4") (pinfunction "VCC_4") (pintype "passive"))
      (node (ref "PAD3") (pin "1") (pinfunction "P_1") (pintype "passive"))
      (node (ref "R11") (pin "2") (pinfunction "2_2") (pintype "passive"))
      (node (ref "R12") (pin "2") (pinfunction "2_2") (pintype "passive"))
      (node (ref "R13") (pin "2") (pinfunction "2_2") (pintype "passive"))
      (node (ref "R15") (pin "2") (pinfunction "2_2") (pintype "passive"))
      (node (ref "R16") (pin "2") (pinfunction "2_2") (pintype "passive"))
      (node (ref "U$1") (pin "P$2") (pinfunction "P$2_P$2") (pintype "bidirectional"))
      (node (ref "U$10") (pin "P$2") (pinfunction "P$2_P$2") (pintype "bidirectional"))
      (node (ref "U$15") (pin "P$16") (pinfunction "VDD_P$16") (pintype "bidirectional"))
      (node (ref "U$16") (pin "P$16") (pinfunction "VDD_P$16") (pintype "bidirectional"))
      (node (ref "U$17") (pin "P$2") (pinfunction "P$2_P$2") (pintype "bidirectional"))
      (node (ref "U$18") (pin "P$2") (pinfunction "P$2_P$2") (pintype "bidirectional"))
      (node (ref "U$19") (pin "P$2") (pinfunction "P$2_P$2") (pintype "bidirectional"))
      (node (ref "U$2") (pin "P$2") (pinfunction "P$2_P$2") (pintype "bidirectional"))
      (node (ref "U$21") (pin "VBUS1") (pinfunction "VBUS1_VBUS1") (pintype "bidirectional"))
      (node (ref "U$21") (pin "VBUS2") (pinfunction "VBUS2_VBUS2") (pintype "bidirectional"))
      (node (ref "U$21") (pin "VBUS3") (pinfunction "VBUS3_VBUS3") (pintype "bidirectional"))
      (node (ref "U$21") (pin "VBUS4") (pinfunction "VBUS4_VBUS4") (pintype "bidirectional"))
      (node (ref "U$3") (pin "P$2") (pinfunction "P$2_P$2") (pintype "bidirectional"))
      (node (ref "U$4") (pin "P$2") (pinfunction "P$2_P$2") (pintype "bidirectional"))
      (node (ref "U$5") (pin "P$2") (pinfunction "P$2_P$2") (pintype "bidirectional"))
      (node (ref "U$6") (pin "P$2") (pinfunction "P$2_P$2") (pintype "bidirectional"))
      (node (ref "U$7") (pin "P$2") (pinfunction "P$2_P$2") (pintype "bidirectional"))
      (node (ref "U$8") (pin "P$2") (pinfunction "P$2_P$2") (pintype "bidirectional"))
      (node (ref "U$9") (pin "P$2") (pinfunction "P$2_P$2") (pintype "bidirectional"))
      (node (ref "U1") (pin "18") (pinfunction "AVCC_18") (pintype "bidirectional"))
      (node (ref "U1") (pin "4") (pinfunction "VCC_4") (pintype "bidirectional"))
      (node (ref "U1") (pin "6") (pinfunction "VCC_6") (pintype "bidirectional"))
    )
    (net (code "88") (name "VCC_33") (class "Default")
      (node (ref "C4") (pin "1") (pinfunction "1_1") (pintype "passive"))
      (node (ref "IC1") (pin "5") (pinfunction "OUT_5") (pintype "output"))
      (node (ref "L1") (pin "1") (pinfunction "1_1") (pintype "passive"))
      (node (ref "SV1") (pin "4") (pinfunction "4_4") (pintype "passive"))
      (node (ref "SV1") (pin "8") (pinfunction "8_8") (pintype "passive"))
    )
    (net (code "89") (name "unconnected-(U$11-PadP$6)") (class "Default")
      (node (ref "U$11") (pin "P$6") (pinfunction "P$6_P$6") (pintype "bidirectional"))
    )
    (net (code "90") (name "unconnected-(U$11-PadP$7)") (class "Default")
      (node (ref "U$11") (pin "P$7") (pinfunction "P$7_P$7") (pintype "bidirectional"))
    )
    (net (code "91") (name "unconnected-(U$11-PadP$8)") (class "Default")
      (node (ref "U$11") (pin "P$8") (pinfunction "P$8_P$8") (pintype "bidirectional"))
    )
    (net (code "92") (name "unconnected-(U$11-PadP$10)") (class "Default")
      (node (ref "U$11") (pin "P$10") (pinfunction "P$10_P$10") (pintype "bidirectional"))
    )
    (net (code "93") (name "unconnected-(U$11-PadP$11)") (class "Default")
      (node (ref "U$11") (pin "P$11") (pinfunction "P$11_P$11") (pintype "bidirectional"))
    )
    (net (code "94") (name "unconnected-(U$11-PadP$12)") (class "Default")
      (node (ref "U$11") (pin "P$12") (pinfunction "P$12_P$12") (pintype "bidirectional"))
    )
    (net (code "95") (name "unconnected-(U$11-PadP$13)") (class "Default")
      (node (ref "U$11") (pin "P$13") (pinfunction "P$13_P$13") (pintype "bidirectional"))
    )
    (net (code "96") (name "unconnected-(U$12-PadP$6)") (class "Default")
      (node (ref "U$12") (pin "P$6") (pinfunction "P$6_P$6") (pintype "bidirectional"))
    )
    (net (code "97") (name "unconnected-(U$12-PadP$7)") (class "Default")
      (node (ref "U$12") (pin "P$7") (pinfunction "P$7_P$7") (pintype "bidirectional"))
    )
    (net (code "98") (name "unconnected-(U$12-PadP$8)") (class "Default")
      (node (ref "U$12") (pin "P$8") (pinfunction "P$8_P$8") (pintype "bidirectional"))
    )
    (net (code "99") (name "unconnected-(U$12-PadP$10)") (class "Default")
      (node (ref "U$12") (pin "P$10") (pinfunction "P$10_P$10") (pintype "bidirectional"))
    )
    (net (code "100") (name "unconnected-(U$12-PadP$11)") (class "Default")
      (node (ref "U$12") (pin "P$11") (pinfunction "P$11_P$11") (pintype "bidirectional"))
    )
    (net (code "101") (name "unconnected-(U$12-PadP$12)") (class "Default")
      (node (ref "U$12") (pin "P$12") (pinfunction "P$12_P$12") (pintype "bidirectional"))
    )
    (net (code "102") (name "unconnected-(U$12-PadP$13)") (class "Default")
      (node (ref "U$12") (pin "P$13") (pinfunction "P$13_P$13") (pintype "bidirectional"))
    )
    (net (code "103") (name "unconnected-(U$15-DOUT-PadP$1)") (class "Default")
      (node (ref "U$15") (pin "P$1") (pinfunction "DOUT_P$1") (pintype "bidirectional"))
    )
    (net (code "104") (name "unconnected-(U$16-DOUT-PadP$1)") (class "Default")
      (node (ref "U$16") (pin "P$1") (pinfunction "DOUT_P$1") (pintype "bidirectional"))
    )
    (net (code "105") (name "unconnected-(U$19-PadP$1)") (class "Default")
      (node (ref "U$19") (pin "P$1") (pinfunction "P$1_P$1") (pintype "bidirectional"))
    )
    (net (code "106") (name "unconnected-(U$19-PadP$3)") (class "Default")
      (node (ref "U$19") (pin "P$3") (pinfunction "P$3_P$3") (pintype "bidirectional"))
    )
    (net (code "107") (name "unconnected-(U$19-PadP$4)") (class "Default")
      (node (ref "U$19") (pin "P$4") (pinfunction "P$4_P$4") (pintype "bidirectional"))
    )
    (net (code "108") (name "unconnected-(U$21-PadCC1)") (class "Default")
      (node (ref "U$21") (pin "CC1") (pinfunction "CC1_CC1") (pintype "bidirectional"))
    )
    (net (code "109") (name "unconnected-(U$21-PadCC2)") (class "Default")
      (node (ref "U$21") (pin "CC2") (pinfunction "CC2_CC2") (pintype "bidirectional"))
    )
    (net (code "110") (name "unconnected-(U$21-PadDN1)") (class "Default")
      (node (ref "U$21") (pin "DN1") (pinfunction "DN1_DN1") (pintype "bidirectional"))
    )
    (net (code "111") (name "unconnected-(U$21-PadDN2)") (class "Default")
      (node (ref "U$21") (pin "DN2") (pinfunction "DN2_DN2") (pintype "bidirectional"))
    )
    (net (code "112") (name "unconnected-(U$21-PadDP1)") (class "Default")
      (node (ref "U$21") (pin "DP1") (pinfunction "DP1_DP1") (pintype "bidirectional"))
    )
    (net (code "113") (name "unconnected-(U$21-PadDP2)") (class "Default")
      (node (ref "U$21") (pin "DP2") (pinfunction "DP2_DP2") (pintype "bidirectional"))
    )
    (net (code "114") (name "unconnected-(U$21-PadSBU1)") (class "Default")
      (node (ref "U$21") (pin "SBU1") (pinfunction "SBU1_SBU1") (pintype "bidirectional"))
    )
    (net (code "115") (name "unconnected-(U$21-PadSBU2)") (class "Default")
      (node (ref "U$21") (pin "SBU2") (pinfunction "SBU2_SBU2") (pintype "bidirectional"))
    )
    (net (code "116") (name "unconnected-(U$21-PadSSRXN1)") (class "Default")
      (node (ref "U$21") (pin "SSRXN1") (pinfunction "SSRXN1_SSRXN1") (pintype "bidirectional"))
    )
    (net (code "117") (name "unconnected-(U$21-PadSSRXN2)") (class "Default")
      (node (ref "U$21") (pin "SSRXN2") (pinfunction "SSRXN2_SSRXN2") (pintype "bidirectional"))
    )
    (net (code "118") (name "unconnected-(U$21-PadSSRXP1)") (class "Default")
      (node (ref "U$21") (pin "SSRXP1") (pinfunction "SSRXP1_SSRXP1") (pintype "bidirectional"))
    )
    (net (code "119") (name "unconnected-(U$21-PadSSRXP2)") (class "Default")
      (node (ref "U$21") (pin "SSRXP2") (pinfunction "SSRXP2_SSRXP2") (pintype "bidirectional"))
    )
    (net (code "120") (name "unconnected-(U$21-PadSSTXN1)") (class "Default")
      (node (ref "U$21") (pin "SSTXN1") (pinfunction "SSTXN1_SSTXN1") (pintype "bidirectional"))
    )
    (net (code "121") (name "unconnected-(U$21-PadSSTXN2)") (class "Default")
      (node (ref "U$21") (pin "SSTXN2") (pinfunction "SSTXN2_SSTXN2") (pintype "bidirectional"))
    )
    (net (code "122") (name "unconnected-(U$21-PadSSTXP1)") (class "Default")
      (node (ref "U$21") (pin "SSTXP1") (pinfunction "SSTXP1_SSTXP1") (pintype "bidirectional"))
    )
    (net (code "123") (name "unconnected-(U$21-PadSSTXP2)") (class "Default")
      (node (ref "U$21") (pin "SSTXP2") (pinfunction "SSTXP2_SSTXP2") (pintype "bidirectional"))
    )
  )
)
